# Watson.net
KiCad netlist of a schematic drawn in EAGLE
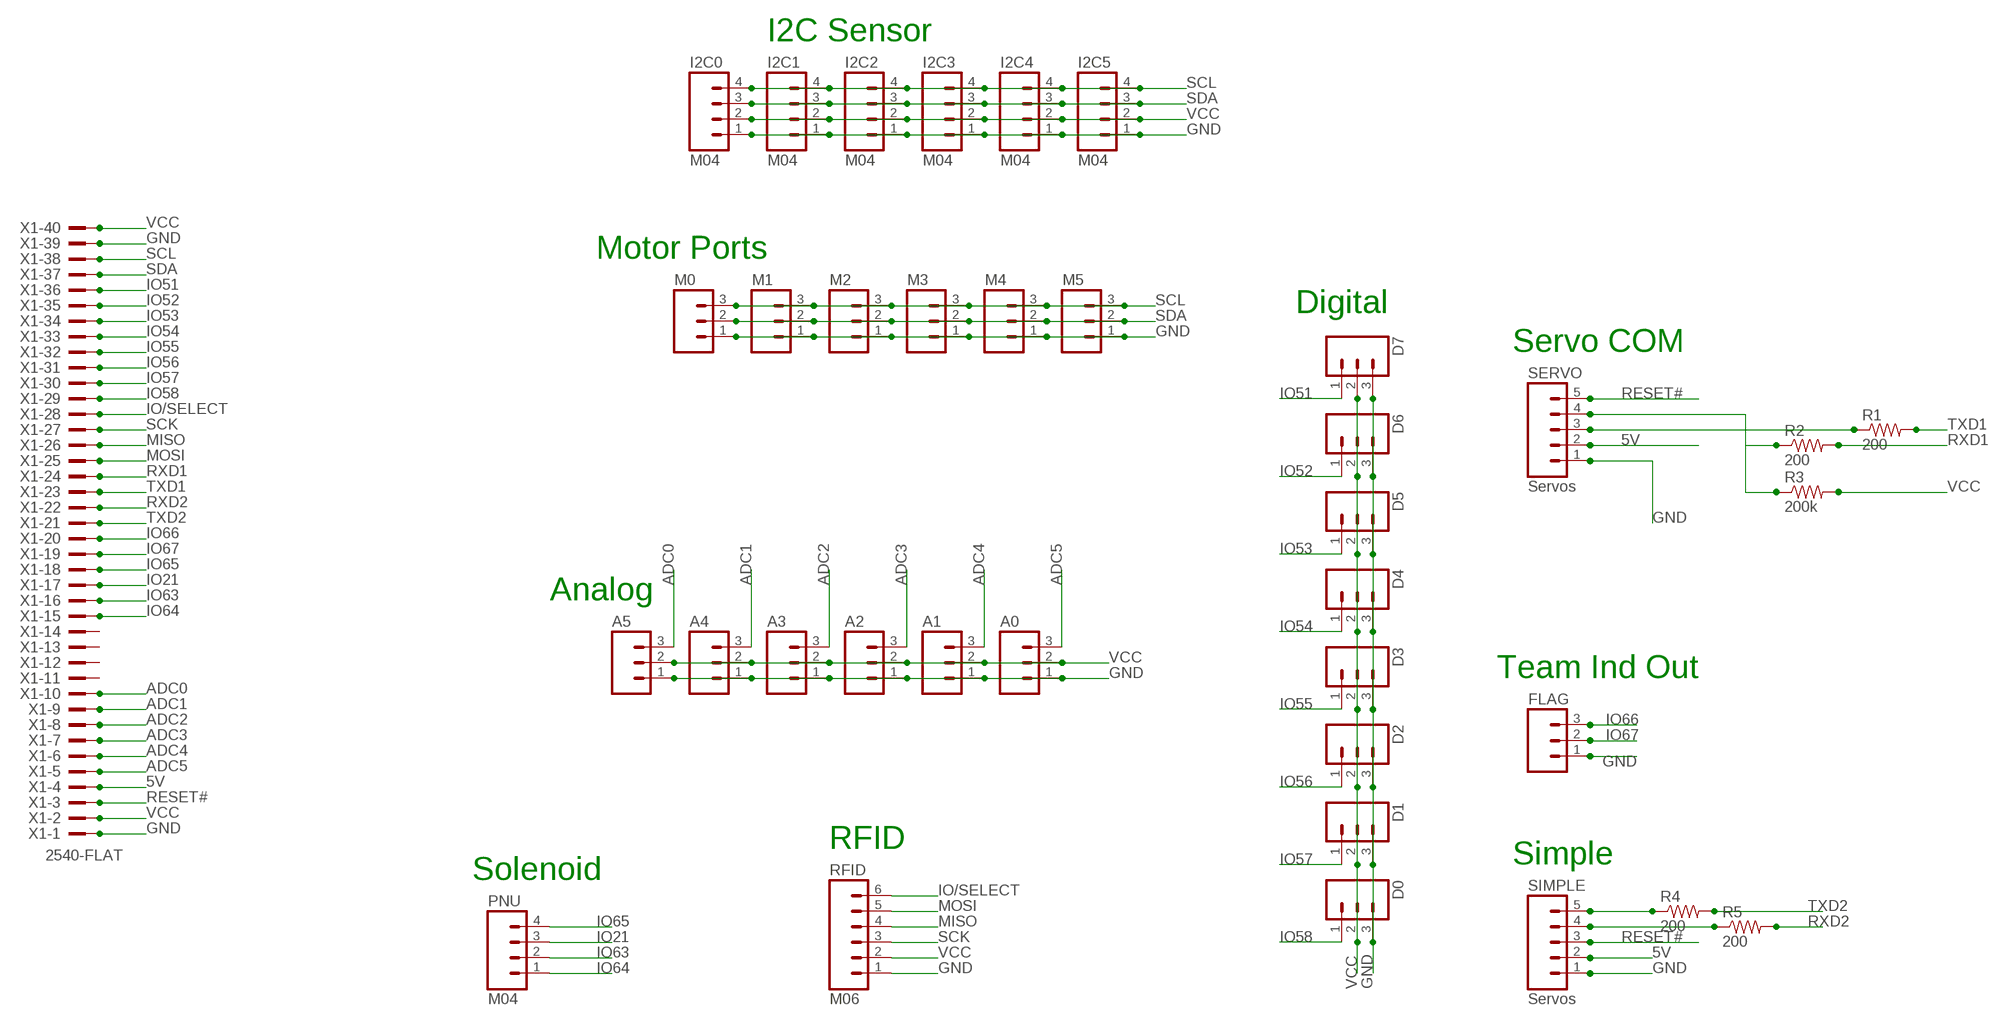
[diagram p0: schematic, sheet 1]

(export (version "E")
  (design (tool "Eeschema 10.0.6"))
  (components
    (comp (ref "A0")
      (value "M03MTA1X3")
      (footprint "eagle-import:1X03")
      (libsource (lib "eagle-import") (part "M03MTA1X3"))
    )
    (comp (ref "A1")
      (value "M03MTA1X3")
      (footprint "eagle-import:1X03")
      (libsource (lib "eagle-import") (part "M03MTA1X3"))
    )
    (comp (ref "A2")
      (value "M03MTA1X3")
      (footprint "eagle-import:1X03")
      (libsource (lib "eagle-import") (part "M03MTA1X3"))
    )
    (comp (ref "A3")
      (value "M03MTA1X3")
      (footprint "eagle-import:1X03")
      (libsource (lib "eagle-import") (part "M03MTA1X3"))
    )
    (comp (ref "A4")
      (value "M03MTA1X3")
      (footprint "eagle-import:1X03")
      (libsource (lib "eagle-import") (part "M03MTA1X3"))
    )
    (comp (ref "A5")
      (value "M03MTA1X3")
      (footprint "eagle-import:1X03")
      (libsource (lib "eagle-import") (part "M03MTA1X3"))
    )
    (comp (ref "D0")
      (value "M03MTA1X3")
      (footprint "eagle-import:1X03")
      (libsource (lib "eagle-import") (part "M03MTA1X3"))
    )
    (comp (ref "D1")
      (value "M03MTA1X3")
      (footprint "eagle-import:1X03")
      (libsource (lib "eagle-import") (part "M03MTA1X3"))
    )
    (comp (ref "D2")
      (value "M03MTA1X3")
      (footprint "eagle-import:1X03")
      (libsource (lib "eagle-import") (part "M03MTA1X3"))
    )
    (comp (ref "D3")
      (value "M03MTA1X3")
      (footprint "eagle-import:1X03")
      (libsource (lib "eagle-import") (part "M03MTA1X3"))
    )
    (comp (ref "D4")
      (value "M03MTA1X3")
      (footprint "eagle-import:1X03")
      (libsource (lib "eagle-import") (part "M03MTA1X3"))
    )
    (comp (ref "D5")
      (value "M03MTA1X3")
      (footprint "eagle-import:1X03")
      (libsource (lib "eagle-import") (part "M03MTA1X3"))
    )
    (comp (ref "D6")
      (value "M03MTA1X3")
      (footprint "eagle-import:1X03")
      (libsource (lib "eagle-import") (part "M03MTA1X3"))
    )
    (comp (ref "D7")
      (value "M03MTA1X3")
      (footprint "eagle-import:1X03")
      (libsource (lib "eagle-import") (part "M03MTA1X3"))
    )
    (comp (ref "FLAG")
      (value "M03MTA1X3")
      (footprint "eagle-import:1X03")
      (libsource (lib "eagle-import") (part "M03MTA1X3"))
    )
    (comp (ref "I2C0")
      (value "M04")
      (footprint "eagle-import:1X04")
      (libsource (lib "eagle-import") (part "M04"))
    )
    (comp (ref "I2C1")
      (value "M04")
      (footprint "eagle-import:1X04")
      (libsource (lib "eagle-import") (part "M04"))
    )
    (comp (ref "I2C2")
      (value "M04")
      (footprint "eagle-import:1X04")
      (libsource (lib "eagle-import") (part "M04"))
    )
    (comp (ref "I2C3")
      (value "M04")
      (footprint "eagle-import:1X04")
      (libsource (lib "eagle-import") (part "M04"))
    )
    (comp (ref "I2C4")
      (value "M04")
      (footprint "eagle-import:1X04")
      (libsource (lib "eagle-import") (part "M04"))
    )
    (comp (ref "I2C5")
      (value "M04")
      (footprint "eagle-import:1X04")
      (libsource (lib "eagle-import") (part "M04"))
    )
    (comp (ref "M0")
      (value "M03MTA1X3")
      (footprint "eagle-import:1X03")
      (libsource (lib "eagle-import") (part "M03MTA1X3"))
    )
    (comp (ref "M1")
      (value "M03MTA1X3")
      (footprint "eagle-import:1X03")
      (libsource (lib "eagle-import") (part "M03MTA1X3"))
    )
    (comp (ref "M2")
      (value "M03MTA1X3")
      (footprint "eagle-import:1X03")
      (libsource (lib "eagle-import") (part "M03MTA1X3"))
    )
    (comp (ref "M3")
      (value "M03MTA1X3")
      (footprint "eagle-import:1X03")
      (libsource (lib "eagle-import") (part "M03MTA1X3"))
    )
    (comp (ref "M4")
      (value "M03MTA1X3")
      (footprint "eagle-import:1X03")
      (libsource (lib "eagle-import") (part "M03MTA1X3"))
    )
    (comp (ref "M5")
      (value "M03MTA1X3")
      (footprint "eagle-import:1X03")
      (libsource (lib "eagle-import") (part "M03MTA1X3"))
    )
    (comp (ref "PNU")
      (value "M04")
      (footprint "eagle-import:1X04")
      (libsource (lib "eagle-import") (part "M04"))
    )
    (comp (ref "R1")
      (value "200")
      (footprint "eagle-import:R0603")
      (libsource (lib "eagle-import") (part "R-US_R0603"))
    )
    (comp (ref "R2")
      (value "200")
      (footprint "eagle-import:R0603")
      (libsource (lib "eagle-import") (part "R-US_R0603"))
    )
    (comp (ref "R3")
      (value "200k")
      (footprint "eagle-import:R0603")
      (libsource (lib "eagle-import") (part "R-US_R0603"))
    )
    (comp (ref "R4")
      (value "200")
      (footprint "eagle-import:R0603")
      (libsource (lib "eagle-import") (part "R-US_R0603"))
    )
    (comp (ref "R5")
      (value "200")
      (footprint "eagle-import:R0603")
      (libsource (lib "eagle-import") (part "R-US_R0603"))
    )
    (comp (ref "RFID")
      (value "M06")
      (footprint "eagle-import:1X06")
      (libsource (lib "eagle-import") (part "M06"))
    )
    (comp (ref "SERVO")
      (value "Servos")
      (footprint "eagle-import:1X05")
      (libsource (lib "eagle-import") (part "M05"))
    )
    (comp (ref "SIMPLE")
      (value "Servos")
      (footprint "eagle-import:1X05")
      (libsource (lib "eagle-import") (part "M05"))
    )
    (comp (ref "X1")
      (value "2540-FLAT")
      (footprint "eagle-import:PAK100_2500-40")
      (fields (field (name "OC_FARNELL") "unknown"))
      (libsource (lib "eagle-import") (part "2540-FLAT"))
    )
  )
  (nets
    (net (code "1") (name "/5V") (class "Default")
      (node (ref "SERVO") (pin "2") (pinfunction "2_2") (pintype "passive"))
      (node (ref "SIMPLE") (pin "2") (pinfunction "2_2") (pintype "passive"))
      (node (ref "X1") (pin "4") (pinfunction "KL_4") (pintype "passive"))
    )
    (net (code "2") (name "/ADC0") (class "Default")
      (node (ref "A5") (pin "3") (pinfunction "3_3") (pintype "passive"))
      (node (ref "X1") (pin "10") (pinfunction "KL_10") (pintype "passive"))
    )
    (net (code "3") (name "/ADC1") (class "Default")
      (node (ref "A4") (pin "3") (pinfunction "3_3") (pintype "passive"))
      (node (ref "X1") (pin "9") (pinfunction "KL_9") (pintype "passive"))
    )
    (net (code "4") (name "/ADC2") (class "Default")
      (node (ref "A3") (pin "3") (pinfunction "3_3") (pintype "passive"))
      (node (ref "X1") (pin "8") (pinfunction "KL_8") (pintype "passive"))
    )
    (net (code "5") (name "/ADC3") (class "Default")
      (node (ref "A2") (pin "3") (pinfunction "3_3") (pintype "passive"))
      (node (ref "X1") (pin "7") (pinfunction "KL_7") (pintype "passive"))
    )
    (net (code "6") (name "/ADC4") (class "Default")
      (node (ref "A1") (pin "3") (pinfunction "3_3") (pintype "passive"))
      (node (ref "X1") (pin "6") (pinfunction "KL_6") (pintype "passive"))
    )
    (net (code "7") (name "/ADC5") (class "Default")
      (node (ref "A0") (pin "3") (pinfunction "3_3") (pintype "passive"))
      (node (ref "X1") (pin "5") (pinfunction "KL_5") (pintype "passive"))
    )
    (net (code "8") (name "/GND") (class "Default")
      (node (ref "A0") (pin "1") (pinfunction "1_1") (pintype "passive"))
      (node (ref "A1") (pin "1") (pinfunction "1_1") (pintype "passive"))
      (node (ref "A2") (pin "1") (pinfunction "1_1") (pintype "passive"))
      (node (ref "A3") (pin "1") (pinfunction "1_1") (pintype "passive"))
      (node (ref "A4") (pin "1") (pinfunction "1_1") (pintype "passive"))
      (node (ref "A5") (pin "1") (pinfunction "1_1") (pintype "passive"))
      (node (ref "D0") (pin "3") (pinfunction "3_3") (pintype "passive"))
      (node (ref "D1") (pin "3") (pinfunction "3_3") (pintype "passive"))
      (node (ref "D2") (pin "3") (pinfunction "3_3") (pintype "passive"))
      (node (ref "D3") (pin "3") (pinfunction "3_3") (pintype "passive"))
      (node (ref "D4") (pin "3") (pinfunction "3_3") (pintype "passive"))
      (node (ref "D5") (pin "3") (pinfunction "3_3") (pintype "passive"))
      (node (ref "D6") (pin "3") (pinfunction "3_3") (pintype "passive"))
      (node (ref "D7") (pin "3") (pinfunction "3_3") (pintype "passive"))
      (node (ref "FLAG") (pin "1") (pinfunction "1_1") (pintype "passive"))
      (node (ref "I2C0") (pin "1") (pinfunction "1_1") (pintype "passive"))
      (node (ref "I2C1") (pin "1") (pinfunction "1_1") (pintype "passive"))
      (node (ref "I2C2") (pin "1") (pinfunction "1_1") (pintype "passive"))
      (node (ref "I2C3") (pin "1") (pinfunction "1_1") (pintype "passive"))
      (node (ref "I2C4") (pin "1") (pinfunction "1_1") (pintype "passive"))
      (node (ref "I2C5") (pin "1") (pinfunction "1_1") (pintype "passive"))
      (node (ref "M0") (pin "1") (pinfunction "1_1") (pintype "passive"))
      (node (ref "M1") (pin "1") (pinfunction "1_1") (pintype "passive"))
      (node (ref "M2") (pin "1") (pinfunction "1_1") (pintype "passive"))
      (node (ref "M3") (pin "1") (pinfunction "1_1") (pintype "passive"))
      (node (ref "M4") (pin "1") (pinfunction "1_1") (pintype "passive"))
      (node (ref "M5") (pin "1") (pinfunction "1_1") (pintype "passive"))
      (node (ref "RFID") (pin "1") (pinfunction "1_1") (pintype "passive"))
      (node (ref "SERVO") (pin "1") (pinfunction "1_1") (pintype "passive"))
      (node (ref "SIMPLE") (pin "1") (pinfunction "1_1") (pintype "passive"))
      (node (ref "X1") (pin "1") (pinfunction "KL_1") (pintype "passive"))
      (node (ref "X1") (pin "39") (pinfunction "KL_39") (pintype "passive"))
    )
    (net (code "9") (name "/IO21") (class "Default")
      (node (ref "PNU") (pin "3") (pinfunction "3_3") (pintype "passive"))
      (node (ref "X1") (pin "17") (pinfunction "KL_17") (pintype "passive"))
    )
    (net (code "10") (name "/IO51") (class "Default")
      (node (ref "D7") (pin "1") (pinfunction "1_1") (pintype "passive"))
      (node (ref "X1") (pin "36") (pinfunction "KL_36") (pintype "passive"))
    )
    (net (code "11") (name "/IO52") (class "Default")
      (node (ref "D6") (pin "1") (pinfunction "1_1") (pintype "passive"))
      (node (ref "X1") (pin "35") (pinfunction "KL_35") (pintype "passive"))
    )
    (net (code "12") (name "/IO53") (class "Default")
      (node (ref "D5") (pin "1") (pinfunction "1_1") (pintype "passive"))
      (node (ref "X1") (pin "34") (pinfunction "KL_34") (pintype "passive"))
    )
    (net (code "13") (name "/IO54") (class "Default")
      (node (ref "D4") (pin "1") (pinfunction "1_1") (pintype "passive"))
      (node (ref "X1") (pin "33") (pinfunction "KL_33") (pintype "passive"))
    )
    (net (code "14") (name "/IO55") (class "Default")
      (node (ref "D3") (pin "1") (pinfunction "1_1") (pintype "passive"))
      (node (ref "X1") (pin "32") (pinfunction "KL_32") (pintype "passive"))
    )
    (net (code "15") (name "/IO56") (class "Default")
      (node (ref "D2") (pin "1") (pinfunction "1_1") (pintype "passive"))
      (node (ref "X1") (pin "31") (pinfunction "KL_31") (pintype "passive"))
    )
    (net (code "16") (name "/IO57") (class "Default")
      (node (ref "D1") (pin "1") (pinfunction "1_1") (pintype "passive"))
      (node (ref "X1") (pin "30") (pinfunction "KL_30") (pintype "passive"))
    )
    (net (code "17") (name "/IO58") (class "Default")
      (node (ref "D0") (pin "1") (pinfunction "1_1") (pintype "passive"))
      (node (ref "X1") (pin "29") (pinfunction "KL_29") (pintype "passive"))
    )
    (net (code "18") (name "/IO63") (class "Default")
      (node (ref "PNU") (pin "2") (pinfunction "2_2") (pintype "passive"))
      (node (ref "X1") (pin "16") (pinfunction "KL_16") (pintype "passive"))
    )
    (net (code "19") (name "/IO64") (class "Default")
      (node (ref "PNU") (pin "1") (pinfunction "1_1") (pintype "passive"))
      (node (ref "X1") (pin "15") (pinfunction "KL_15") (pintype "passive"))
    )
    (net (code "20") (name "/IO65") (class "Default")
      (node (ref "PNU") (pin "4") (pinfunction "4_4") (pintype "passive"))
      (node (ref "X1") (pin "18") (pinfunction "KL_18") (pintype "passive"))
    )
    (net (code "21") (name "/IO66") (class "Default")
      (node (ref "FLAG") (pin "3") (pinfunction "3_3") (pintype "passive"))
      (node (ref "X1") (pin "20") (pinfunction "KL_20") (pintype "passive"))
    )
    (net (code "22") (name "/IO67") (class "Default")
      (node (ref "FLAG") (pin "2") (pinfunction "2_2") (pintype "passive"))
      (node (ref "X1") (pin "19") (pinfunction "KL_19") (pintype "passive"))
    )
    (net (code "23") (name "/IO{slash}SELECT") (class "Default")
      (node (ref "RFID") (pin "6") (pinfunction "6_6") (pintype "passive"))
      (node (ref "X1") (pin "28") (pinfunction "KL_28") (pintype "passive"))
    )
    (net (code "24") (name "/MISO") (class "Default")
      (node (ref "RFID") (pin "4") (pinfunction "4_4") (pintype "passive"))
      (node (ref "X1") (pin "26") (pinfunction "KL_26") (pintype "passive"))
    )
    (net (code "25") (name "/MOSI") (class "Default")
      (node (ref "RFID") (pin "5") (pinfunction "5_5") (pintype "passive"))
      (node (ref "X1") (pin "25") (pinfunction "KL_25") (pintype "passive"))
    )
    (net (code "26") (name "/RESET#") (class "Default")
      (node (ref "SERVO") (pin "5") (pinfunction "5_5") (pintype "passive"))
      (node (ref "SIMPLE") (pin "3") (pinfunction "3_3") (pintype "passive"))
      (node (ref "X1") (pin "3") (pinfunction "KL_3") (pintype "passive"))
    )
    (net (code "27") (name "/RXD1") (class "Default")
      (node (ref "R2") (pin "2") (pinfunction "2_2") (pintype "passive"))
      (node (ref "X1") (pin "24") (pinfunction "KL_24") (pintype "passive"))
    )
    (net (code "28") (name "/RXD2") (class "Default")
      (node (ref "R5") (pin "2") (pinfunction "2_2") (pintype "passive"))
      (node (ref "X1") (pin "22") (pinfunction "KL_22") (pintype "passive"))
    )
    (net (code "29") (name "/SCK") (class "Default")
      (node (ref "RFID") (pin "3") (pinfunction "3_3") (pintype "passive"))
      (node (ref "X1") (pin "27") (pinfunction "KL_27") (pintype "passive"))
    )
    (net (code "30") (name "/SCL") (class "Default")
      (node (ref "I2C0") (pin "4") (pinfunction "4_4") (pintype "passive"))
      (node (ref "I2C1") (pin "4") (pinfunction "4_4") (pintype "passive"))
      (node (ref "I2C2") (pin "4") (pinfunction "4_4") (pintype "passive"))
      (node (ref "I2C3") (pin "4") (pinfunction "4_4") (pintype "passive"))
      (node (ref "I2C4") (pin "4") (pinfunction "4_4") (pintype "passive"))
      (node (ref "I2C5") (pin "4") (pinfunction "4_4") (pintype "passive"))
      (node (ref "M0") (pin "3") (pinfunction "3_3") (pintype "passive"))
      (node (ref "M1") (pin "3") (pinfunction "3_3") (pintype "passive"))
      (node (ref "M2") (pin "3") (pinfunction "3_3") (pintype "passive"))
      (node (ref "M3") (pin "3") (pinfunction "3_3") (pintype "passive"))
      (node (ref "M4") (pin "3") (pinfunction "3_3") (pintype "passive"))
      (node (ref "M5") (pin "3") (pinfunction "3_3") (pintype "passive"))
      (node (ref "X1") (pin "38") (pinfunction "KL_38") (pintype "passive"))
    )
    (net (code "31") (name "/SDA") (class "Default")
      (node (ref "I2C0") (pin "3") (pinfunction "3_3") (pintype "passive"))
      (node (ref "I2C1") (pin "3") (pinfunction "3_3") (pintype "passive"))
      (node (ref "I2C2") (pin "3") (pinfunction "3_3") (pintype "passive"))
      (node (ref "I2C3") (pin "3") (pinfunction "3_3") (pintype "passive"))
      (node (ref "I2C4") (pin "3") (pinfunction "3_3") (pintype "passive"))
      (node (ref "I2C5") (pin "3") (pinfunction "3_3") (pintype "passive"))
      (node (ref "M0") (pin "2") (pinfunction "2_2") (pintype "passive"))
      (node (ref "M1") (pin "2") (pinfunction "2_2") (pintype "passive"))
      (node (ref "M2") (pin "2") (pinfunction "2_2") (pintype "passive"))
      (node (ref "M3") (pin "2") (pinfunction "2_2") (pintype "passive"))
      (node (ref "M4") (pin "2") (pinfunction "2_2") (pintype "passive"))
      (node (ref "M5") (pin "2") (pinfunction "2_2") (pintype "passive"))
      (node (ref "X1") (pin "37") (pinfunction "KL_37") (pintype "passive"))
    )
    (net (code "32") (name "/TXD1") (class "Default")
      (node (ref "R1") (pin "2") (pinfunction "2_2") (pintype "passive"))
      (node (ref "X1") (pin "23") (pinfunction "KL_23") (pintype "passive"))
    )
    (net (code "33") (name "/TXD2") (class "Default")
      (node (ref "R4") (pin "2") (pinfunction "2_2") (pintype "passive"))
      (node (ref "X1") (pin "21") (pinfunction "KL_21") (pintype "passive"))
    )
    (net (code "34") (name "/VCC") (class "Default")
      (node (ref "A0") (pin "2") (pinfunction "2_2") (pintype "passive"))
      (node (ref "A1") (pin "2") (pinfunction "2_2") (pintype "passive"))
      (node (ref "A2") (pin "2") (pinfunction "2_2") (pintype "passive"))
      (node (ref "A3") (pin "2") (pinfunction "2_2") (pintype "passive"))
      (node (ref "A4") (pin "2") (pinfunction "2_2") (pintype "passive"))
      (node (ref "A5") (pin "2") (pinfunction "2_2") (pintype "passive"))
      (node (ref "D0") (pin "2") (pinfunction "2_2") (pintype "passive"))
      (node (ref "D1") (pin "2") (pinfunction "2_2") (pintype "passive"))
      (node (ref "D2") (pin "2") (pinfunction "2_2") (pintype "passive"))
      (node (ref "D3") (pin "2") (pinfunction "2_2") (pintype "passive"))
      (node (ref "D4") (pin "2") (pinfunction "2_2") (pintype "passive"))
      (node (ref "D5") (pin "2") (pinfunction "2_2") (pintype "passive"))
      (node (ref "D6") (pin "2") (pinfunction "2_2") (pintype "passive"))
      (node (ref "D7") (pin "2") (pinfunction "2_2") (pintype "passive"))
      (node (ref "I2C0") (pin "2") (pinfunction "2_2") (pintype "passive"))
      (node (ref "I2C1") (pin "2") (pinfunction "2_2") (pintype "passive"))
      (node (ref "I2C2") (pin "2") (pinfunction "2_2") (pintype "passive"))
      (node (ref "I2C3") (pin "2") (pinfunction "2_2") (pintype "passive"))
      (node (ref "I2C4") (pin "2") (pinfunction "2_2") (pintype "passive"))
      (node (ref "I2C5") (pin "2") (pinfunction "2_2") (pintype "passive"))
      (node (ref "R3") (pin "2") (pinfunction "2_2") (pintype "passive"))
      (node (ref "RFID") (pin "2") (pinfunction "2_2") (pintype "passive"))
      (node (ref "X1") (pin "2") (pinfunction "KL_2") (pintype "passive"))
      (node (ref "X1") (pin "40") (pinfunction "KL_40") (pintype "passive"))
    )
    (net (code "35") (name "Net-(R1-Pad1)") (class "Default")
      (node (ref "R1") (pin "1") (pinfunction "1_1") (pintype "passive"))
      (node (ref "SERVO") (pin "3") (pinfunction "3_3") (pintype "passive"))
    )
    (net (code "36") (name "Net-(R2-Pad1)") (class "Default")
      (node (ref "R2") (pin "1") (pinfunction "1_1") (pintype "passive"))
      (node (ref "R3") (pin "1") (pinfunction "1_1") (pintype "passive"))
      (node (ref "SERVO") (pin "4") (pinfunction "4_4") (pintype "passive"))
    )
    (net (code "37") (name "Net-(R4-Pad1)") (class "Default")
      (node (ref "R4") (pin "1") (pinfunction "1_1") (pintype "passive"))
      (node (ref "SIMPLE") (pin "5") (pinfunction "5_5") (pintype "passive"))
    )
    (net (code "38") (name "Net-(R5-Pad1)") (class "Default")
      (node (ref "R5") (pin "1") (pinfunction "1_1") (pintype "passive"))
      (node (ref "SIMPLE") (pin "4") (pinfunction "4_4") (pintype "passive"))
    )
    (net (code "39") (name "unconnected-(X1C-KL-Pad11)") (class "Default")
      (node (ref "X1") (pin "11") (pinfunction "KL_11") (pintype "passive"))
    )
    (net (code "40") (name "unconnected-(X1D-KL-Pad12)") (class "Default")
      (node (ref "X1") (pin "12") (pinfunction "KL_12") (pintype "passive"))
    )
    (net (code "41") (name "unconnected-(X1E-KL-Pad13)") (class "Default")
      (node (ref "X1") (pin "13") (pinfunction "KL_13") (pintype "passive"))
    )
    (net (code "42") (name "unconnected-(X1F-KL-Pad14)") (class "Default")
      (node (ref "X1") (pin "14") (pinfunction "KL_14") (pintype "passive"))
    )
  )
)
